# PS_DC-DC_15V_24V.net
KiCad netlist of a schematic drawn in Altium Designer
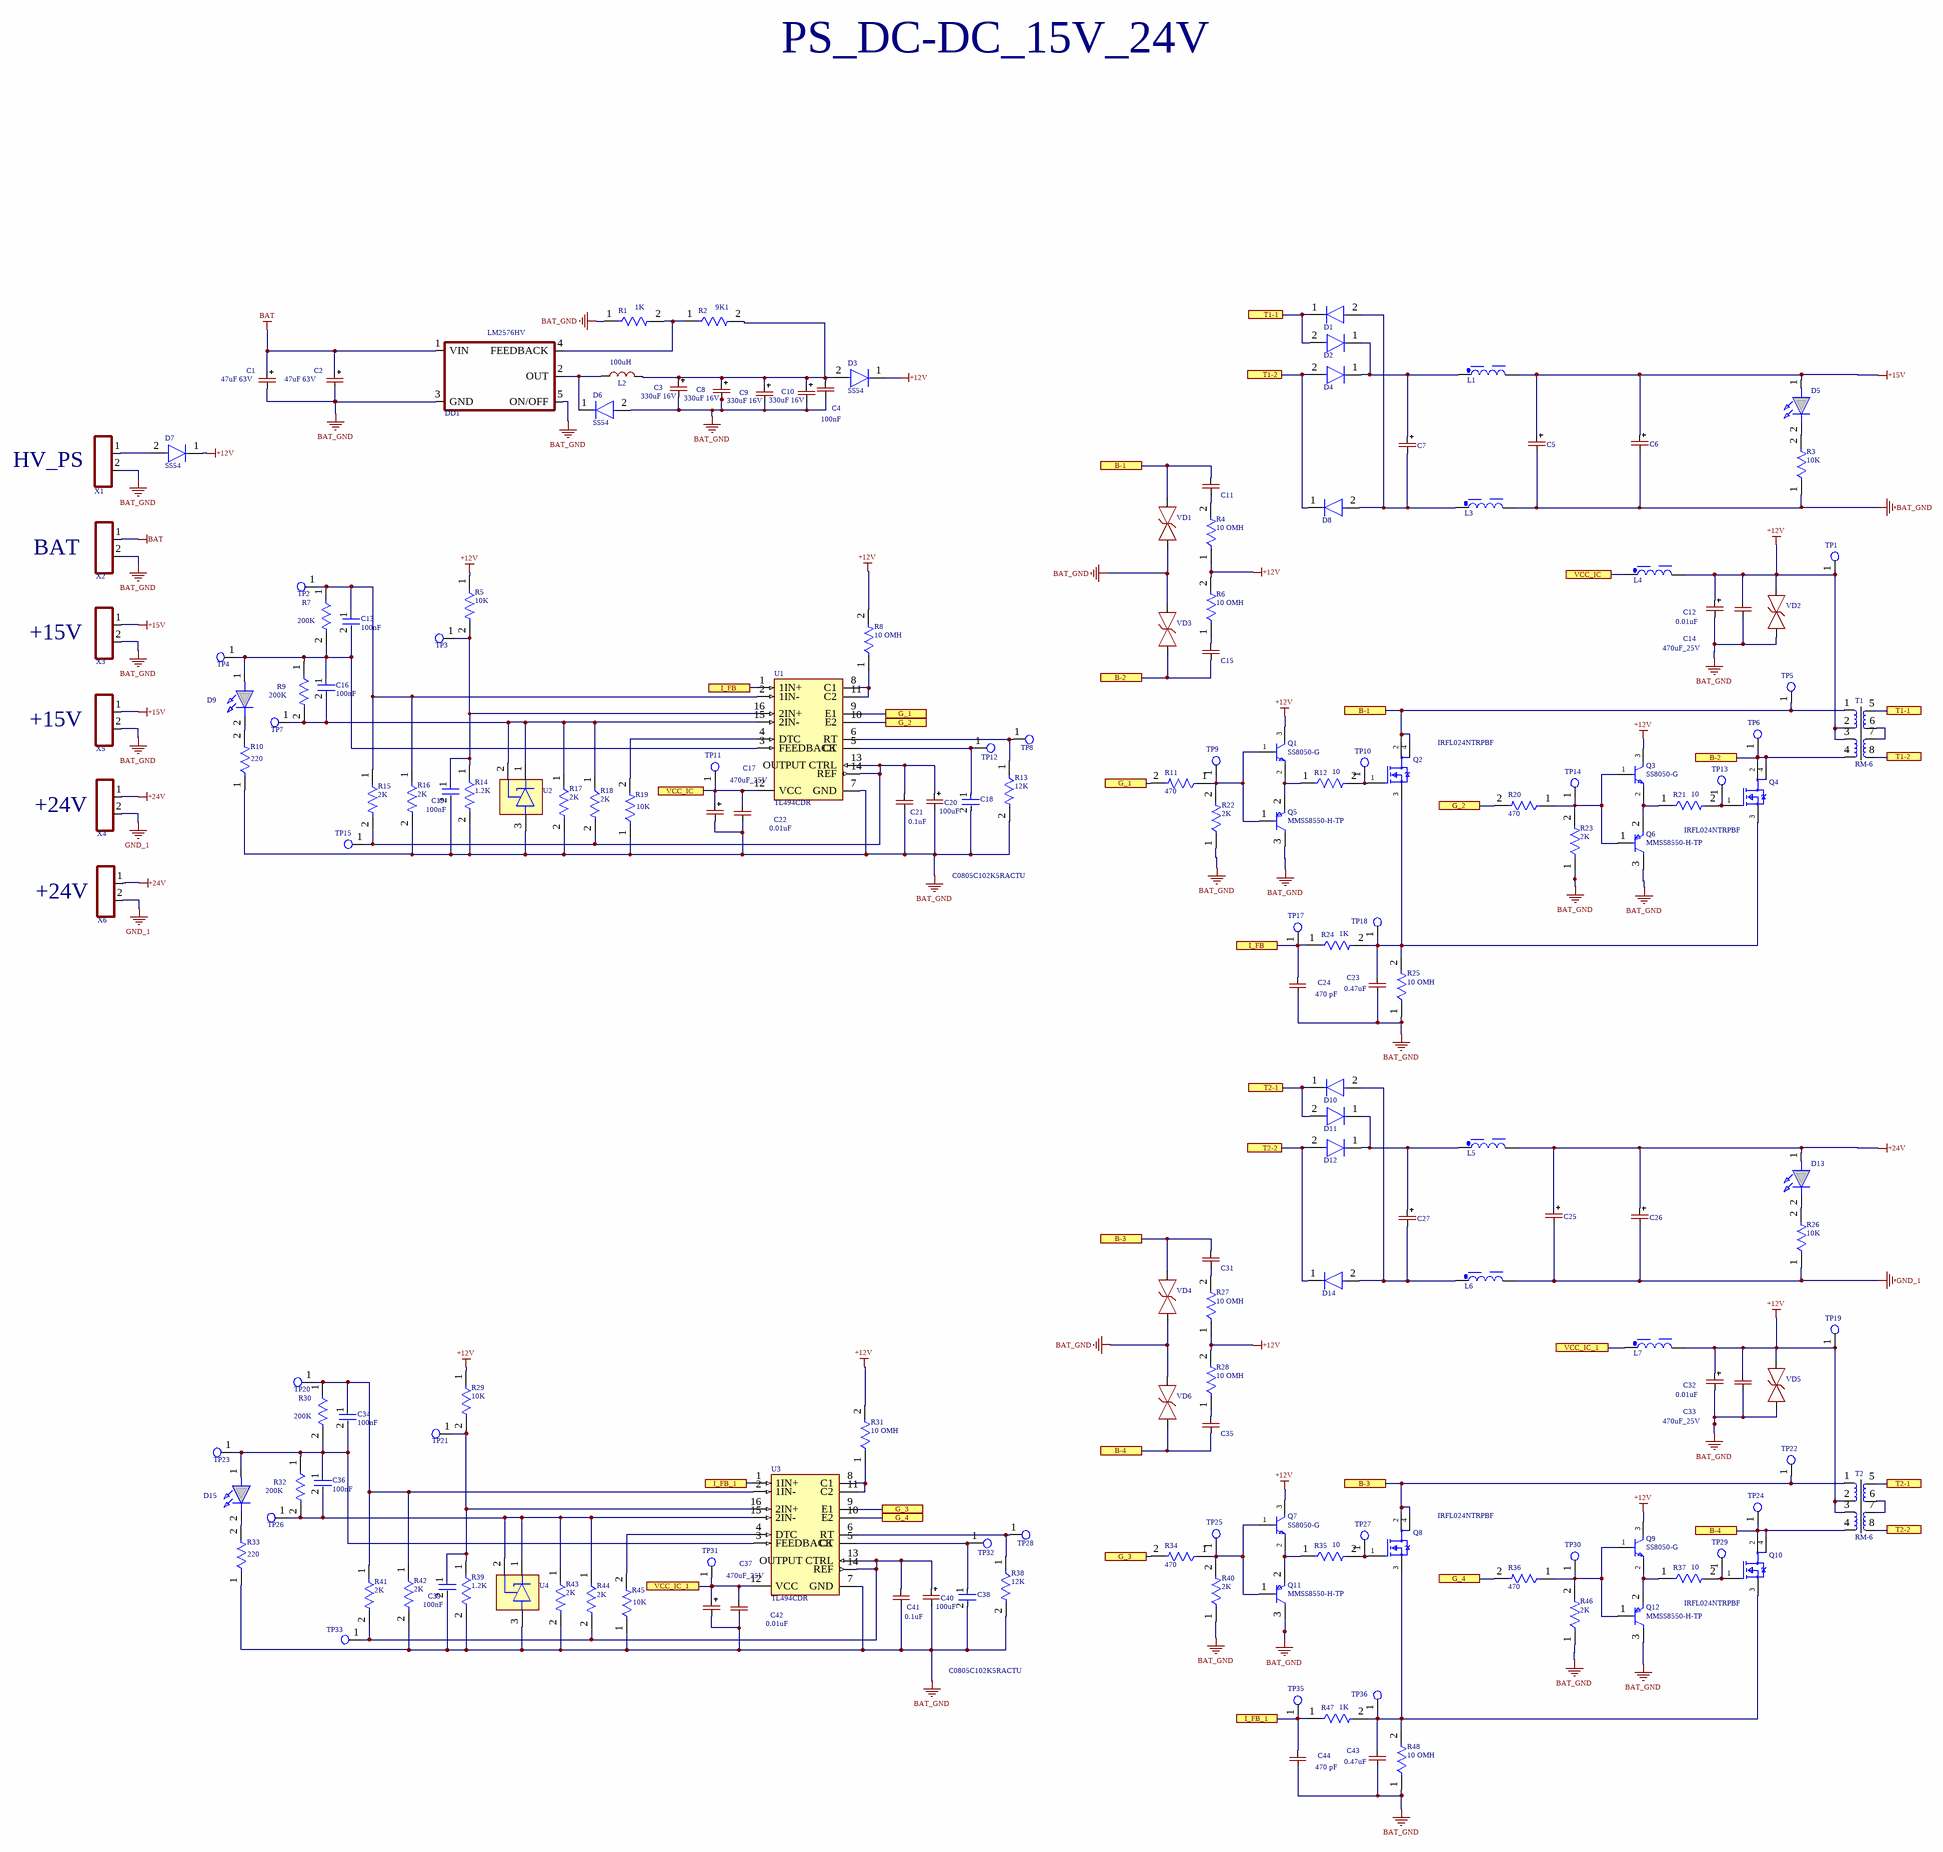
[diagram p0: PS_DC-DC_15V_24V.SchDoc]

(export (version "E")
  (design (tool "Eeschema 10.0.6"))
  (components
    (comp (ref "C1")
      (value "47uF 63V")
      (footprint "CAP_SMD_Size_E")
      (libsource (lib "PASSIVE_COMPONENTS") (part "CAP_POL_SMD"))
    )
    (comp (ref "C2")
      (value "47uF 63V")
      (footprint "CAP_SMD_Size_E")
      (libsource (lib "PASSIVE_COMPONENTS") (part "CAP_POL_SMD"))
    )
    (comp (ref "C3")
      (value "330uF 16V")
      (footprint "CAP_SMD_Size_E")
      (libsource (lib "PASSIVE_COMPONENTS") (part "CAP_POL_SMD"))
    )
    (comp (ref "C4")
      (value "100nF")
      (footprint "CAP-0805")
      (description "1uF ±10% 50V X5R 0805 Multilayer Ceramic Capacitors MLCC - SMD/SMT RoHS")
      (fields (field (name "PART NUMBER") "CC0805KKX5R9BB105") (field (name "MANUFACTURER") "Yageo"))
      (libsource (lib "Database_Libs2") (part "CAP-NON-POLAR"))
    )
    (comp (ref "C5")
      (value "CAP-POLAR")
      (footprint "CAP_SMD_Size_G")
      (libsource (lib "PASSIVE_COMPONENTS") (part "CAP-POLAR"))
    )
    (comp (ref "C6")
      (value "CAP-POLAR")
      (footprint "CAP_SMD_Size_G")
      (libsource (lib "PASSIVE_COMPONENTS") (part "CAP-POLAR"))
    )
    (comp (ref "C7")
      (value "CAP-POLAR")
      (footprint "CAP_SMD_Size_G")
      (libsource (lib "PASSIVE_COMPONENTS") (part "CAP-POLAR"))
    )
    (comp (ref "C8")
      (value "330uF 16V")
      (footprint "CAP_SMD_Size_E")
      (libsource (lib "PASSIVE_COMPONENTS") (part "CAP_POL_SMD"))
    )
    (comp (ref "C9")
      (value "330uF 16V")
      (footprint "CAP_SMD_Size_E")
      (libsource (lib "PASSIVE_COMPONENTS") (part "CAP_POL_SMD"))
    )
    (comp (ref "C10")
      (value "330uF 16V")
      (footprint "CAP_SMD_Size_E")
      (libsource (lib "PASSIVE_COMPONENTS") (part "CAP_POL_SMD"))
    )
    (comp (ref "C11")
      (value "CAP-V")
      (footprint "CAP-V")
      (libsource (lib "PASSIVE_COMPONENTS") (part "CAP-V"))
    )
    (comp (ref "C12")
      (value "0.01uF")
      (footprint "CAP-0805")
      (libsource (lib "PASSIVE_COMPONENTS") (part "CAP-NON-POLAR"))
    )
    (comp (ref "C13")
      (value "100nF")
      (footprint "FP-C0805C-DN-MFG")
      (description "CAP CER 10000PF 50V X7R 0805")
      (fields
        (field (name "MANUFACTURER PART NUMBER") "C0805C103J5RACTU")
        (field (name "MANUFACTURER") "KEMET")
      )
      (libsource (lib "Altium Content Vault") (part "b4654b650e69147ec39a6b967a45e02"))
    )
    (comp (ref "C14")
      (value "470uF_25V")
      (footprint "CAP_SMD_Size_G")
      (libsource (lib "PASSIVE_COMPONENTS") (part "CAP-POLAR"))
    )
    (comp (ref "C15")
      (value "CAP-V")
      (footprint "CAP-V")
      (libsource (lib "PASSIVE_COMPONENTS") (part "CAP-V"))
    )
    (comp (ref "C16")
      (value "100nF")
      (footprint "FP-C0805C-DN-MFG")
      (description "CAP CER 10000PF 50V X7R 0805")
      (fields
        (field (name "MANUFACTURER PART NUMBER") "C0805C103J5RACTU")
        (field (name "MANUFACTURER") "KEMET")
      )
      (libsource (lib "Altium Content Vault") (part "b4654b650e69147ec39a6b967a45e02"))
    )
    (comp (ref "C17")
      (value "470uF_25V")
      (footprint "CAP_SMD_Size_G")
      (libsource (lib "PASSIVE_COMPONENTS") (part "CAP-POLAR"))
    )
    (comp (ref "C18")
      (value "C0805C102K5RACTU")
      (footprint "FP-C0805C-DN-MFG")
      (description "CAP CER 1000PF 50V X7R 0805")
      (fields
        (field (name "OCTOPART") "https://octopart.com/c0805c102k5ractu-kemet-93010")
        (field (name "TOLERANCE") "0.1")
      )
      (libsource (lib "Altium Content Vault") (part "b4654b650e69147ec39a6b967a45e02"))
    )
    (comp (ref "C19")
      (value "100nF")
      (footprint "FP-C0805C-DN-MFG")
      (description "CAP CER 10000PF 50V X7R 0805")
      (fields
        (field (name "MANUFACTURER PART NUMBER") "C0805C103J5RACTU")
        (field (name "MANUFACTURER") "KEMET")
      )
      (libsource (lib "Altium Content Vault") (part "b4654b650e69147ec39a6b967a45e02"))
    )
    (comp (ref "C20")
      (value "100uF")
      (footprint "CAP-TAN-D")
      (libsource (lib "PASSIVE_COMPONENTS") (part "CAP-POLAR"))
    )
    (comp (ref "C21")
      (value "0.1uF")
      (footprint "CAP-0805")
      (libsource (lib "PASSIVE_COMPONENTS") (part "CAP-NON-POLAR"))
    )
    (comp (ref "C22")
      (value "0.01uF")
      (footprint "CAP-0805")
      (libsource (lib "PASSIVE_COMPONENTS") (part "CAP-NON-POLAR"))
    )
    (comp (ref "C23")
      (value "0.47uF")
      (footprint "CAP-0805")
      (libsource (lib "PASSIVE_COMPONENTS") (part "CAP-NON-POLAR"))
    )
    (comp (ref "C24")
      (value "470 pF")
      (footprint "CAP-0805")
      (libsource (lib "PASSIVE_COMPONENTS") (part "CAP-NON-POLAR"))
    )
    (comp (ref "C25")
      (value "CAP-POLAR")
      (footprint "CAP_SMD_Size_G")
      (libsource (lib "PASSIVE_COMPONENTS") (part "CAP-POLAR"))
    )
    (comp (ref "C26")
      (value "CAP-POLAR")
      (footprint "CAP_SMD_Size_G")
      (libsource (lib "PASSIVE_COMPONENTS") (part "CAP-POLAR"))
    )
    (comp (ref "C27")
      (value "CAP-POLAR")
      (footprint "CAP_SMD_Size_G")
      (libsource (lib "PASSIVE_COMPONENTS") (part "CAP-POLAR"))
    )
    (comp (ref "C31")
      (value "CAP-V")
      (footprint "CAP-V")
      (libsource (lib "PASSIVE_COMPONENTS") (part "CAP-V"))
    )
    (comp (ref "C32")
      (value "0.01uF")
      (footprint "CAP-0805")
      (libsource (lib "PASSIVE_COMPONENTS") (part "CAP-NON-POLAR"))
    )
    (comp (ref "C33")
      (value "470uF_25V")
      (footprint "CAP_SMD_Size_G")
      (libsource (lib "PASSIVE_COMPONENTS") (part "CAP-POLAR"))
    )
    (comp (ref "C34")
      (value "100nF")
      (footprint "FP-C0805C-DN-MFG")
      (description "CAP CER 10000PF 50V X7R 0805")
      (fields
        (field (name "MANUFACTURER PART NUMBER") "C0805C103J5RACTU")
        (field (name "MANUFACTURER") "KEMET")
      )
      (libsource (lib "Altium Content Vault") (part "b4654b650e69147ec39a6b967a45e02"))
    )
    (comp (ref "C35")
      (value "CAP-V")
      (footprint "CAP-V")
      (libsource (lib "PASSIVE_COMPONENTS") (part "CAP-V"))
    )
    (comp (ref "C36")
      (value "100nF")
      (footprint "FP-C0805C-DN-MFG")
      (description "CAP CER 10000PF 50V X7R 0805")
      (fields
        (field (name "MANUFACTURER PART NUMBER") "C0805C103J5RACTU")
        (field (name "MANUFACTURER") "KEMET")
      )
      (libsource (lib "Altium Content Vault") (part "b4654b650e69147ec39a6b967a45e02"))
    )
    (comp (ref "C37")
      (value "470uF_25V")
      (footprint "CAP_SMD_Size_G")
      (libsource (lib "PASSIVE_COMPONENTS") (part "CAP-POLAR"))
    )
    (comp (ref "C38")
      (value "C0805C102K5RACTU")
      (footprint "FP-C0805C-DN-MFG")
      (description "CAP CER 1000PF 50V X7R 0805")
      (fields
        (field (name "OCTOPART") "https://octopart.com/c0805c102k5ractu-kemet-93010")
        (field (name "TOLERANCE") "0.1")
      )
      (libsource (lib "Altium Content Vault") (part "b4654b650e69147ec39a6b967a45e02"))
    )
    (comp (ref "C39")
      (value "100nF")
      (footprint "FP-C0805C-DN-MFG")
      (description "CAP CER 10000PF 50V X7R 0805")
      (fields
        (field (name "MANUFACTURER PART NUMBER") "C0805C103J5RACTU")
        (field (name "MANUFACTURER") "KEMET")
      )
      (libsource (lib "Altium Content Vault") (part "b4654b650e69147ec39a6b967a45e02"))
    )
    (comp (ref "C40")
      (value "100uF")
      (footprint "CAP-TAN-D")
      (libsource (lib "PASSIVE_COMPONENTS") (part "CAP-POLAR"))
    )
    (comp (ref "C41")
      (value "0.1uF")
      (footprint "CAP-0805")
      (libsource (lib "PASSIVE_COMPONENTS") (part "CAP-NON-POLAR"))
    )
    (comp (ref "C42")
      (value "0.01uF")
      (footprint "CAP-0805")
      (libsource (lib "PASSIVE_COMPONENTS") (part "CAP-NON-POLAR"))
    )
    (comp (ref "C43")
      (value "0.47uF")
      (footprint "CAP-0805")
      (libsource (lib "PASSIVE_COMPONENTS") (part "CAP-NON-POLAR"))
    )
    (comp (ref "C44")
      (value "470 pF")
      (footprint "CAP-0805")
      (libsource (lib "PASSIVE_COMPONENTS") (part "CAP-NON-POLAR"))
    )
    (comp (ref "D1") (value "US1G") (footprint "DO-214AA") (libsource (lib "Diodes") (part "US1G")))
    (comp (ref "D2") (value "US1G") (footprint "DO-214AA") (libsource (lib "Diodes") (part "US1G")))
    (comp (ref "D3")
      (value "SS54")
      (footprint "DO214-AB")
      (description "ES3D-DO214AB")
      (libsource (lib "Diodes") (part "ES3D-DO214AB"))
    )
    (comp (ref "D4") (value "US1G") (footprint "DO-214AA") (libsource (lib "Diodes") (part "US1G")))
    (comp (ref "D5")
      (value "151031YS06000")
      (footprint "LED_RED")
      (description "WURTH ELEKTRONIK - 151031YS06000 - LED, Yellow, Through Hole, T-1 (3mm), 30 mA, 2 V, 590 nm")
      (fields (field (name "MOUSER PART NUMBER") "710-151031YS06000"))
      (libsource (lib "Optic-LED") (part "LED"))
    )
    (comp (ref "D6")
      (value "SS54")
      (footprint "DO214-AB")
      (description "ES3D-DO214AB")
      (libsource (lib "Diodes") (part "ES3D-DO214AB"))
    )
    (comp (ref "D7")
      (value "SS54")
      (footprint "DO214-AB")
      (description "ES3D-DO214AB")
      (libsource (lib "Diodes") (part "ES3D-DO214AB"))
    )
    (comp (ref "D8") (value "US1G") (footprint "DO-214AA") (libsource (lib "Diodes") (part "US1G")))
    (comp (ref "D9")
      (value "151031YS06000")
      (footprint "LED_RED")
      (description "WURTH ELEKTRONIK - 151031YS06000 - LED, Yellow, Through Hole, T-1 (3mm), 30 mA, 2 V, 590 nm")
      (fields (field (name "MOUSER PART NUMBER") "710-151031YS06000"))
      (libsource (lib "Optic-LED") (part "LED"))
    )
    (comp (ref "D10") (value "US1G") (footprint "DO-214AA") (libsource (lib "Diodes") (part "US1G")))
    (comp (ref "D11") (value "US1G") (footprint "DO-214AA") (libsource (lib "Diodes") (part "US1G")))
    (comp (ref "D12") (value "US1G") (footprint "DO-214AA") (libsource (lib "Diodes") (part "US1G")))
    (comp (ref "D13")
      (value "151031YS06000")
      (footprint "LED_RED")
      (description "WURTH ELEKTRONIK - 151031YS06000 - LED, Yellow, Through Hole, T-1 (3mm), 30 mA, 2 V, 590 nm")
      (fields (field (name "MOUSER PART NUMBER") "710-151031YS06000"))
      (libsource (lib "Optic-LED") (part "LED"))
    )
    (comp (ref "D14") (value "US1G") (footprint "DO-214AA") (libsource (lib "Diodes") (part "US1G")))
    (comp (ref "D15")
      (value "151031YS06000")
      (footprint "LED_RED")
      (description "WURTH ELEKTRONIK - 151031YS06000 - LED, Yellow, Through Hole, T-1 (3mm), 30 mA, 2 V, 590 nm")
      (fields (field (name "MOUSER PART NUMBER") "710-151031YS06000"))
      (libsource (lib "Optic-LED") (part "LED"))
    )
    (comp (ref "DD1")
      (value "LM2576HV")
      (footprint "TO-263-5")
      (libsource (lib "LM2576HV") (part "LM2576HV"))
    )
    (comp (ref "L1")
      (value "390µH, 0.38A")
      (footprint "WE-PD2_7850")
      (description "WE-PD2 SMT Power Inductor, size 7850, 390µH, 0.38A, 1.77Ω")
      (fields
        (field (name "MANUFACTURER PART NUMBER") "744775239")
        (field (name "MANUFACTURER") "Wurth Elektronik")
      )
      (libsource (lib "WE-PD2 (rev22d)") (part "744775239"))
    )
    (comp (ref "L2") (value "100uH") (footprint "CDRH127") (libsource (lib "CDRH127") (part "IND-CONST")))
    (comp (ref "L3")
      (value "390µH, 0.38A")
      (footprint "WE-PD2_7850")
      (description "WE-PD2 SMT Power Inductor, size 7850, 390µH, 0.38A, 1.77Ω")
      (fields
        (field (name "MANUFACTURER PART NUMBER") "744775239")
        (field (name "MANUFACTURER") "Wurth Elektronik")
      )
      (libsource (lib "WE-PD2 (rev22d)") (part "744775239"))
    )
    (comp (ref "L4")
      (value "390µH, 0.38A")
      (footprint "WE-PD2_7850")
      (description "WE-PD2 SMT Power Inductor, size 7850, 390µH, 0.38A, 1.77Ω")
      (fields
        (field (name "MANUFACTURER PART NUMBER") "744775239")
        (field (name "MANUFACTURER") "Wurth Elektronik")
      )
      (libsource (lib "WE-PD2 (rev22d)") (part "744775239"))
    )
    (comp (ref "L5")
      (value "390µH, 0.38A")
      (footprint "WE-PD2_7850")
      (description "WE-PD2 SMT Power Inductor, size 7850, 390µH, 0.38A, 1.77Ω")
      (fields
        (field (name "MANUFACTURER PART NUMBER") "744775239")
        (field (name "MANUFACTURER") "Wurth Elektronik")
      )
      (libsource (lib "WE-PD2 (rev22d)") (part "744775239"))
    )
    (comp (ref "L6")
      (value "390µH, 0.38A")
      (footprint "WE-PD2_7850")
      (description "WE-PD2 SMT Power Inductor, size 7850, 390µH, 0.38A, 1.77Ω")
      (fields
        (field (name "MANUFACTURER PART NUMBER") "744775239")
        (field (name "MANUFACTURER") "Wurth Elektronik")
      )
      (libsource (lib "WE-PD2 (rev22d)") (part "744775239"))
    )
    (comp (ref "L7")
      (value "390µH, 0.38A")
      (footprint "WE-PD2_7850")
      (description "WE-PD2 SMT Power Inductor, size 7850, 390µH, 0.38A, 1.77Ω")
      (fields
        (field (name "MANUFACTURER PART NUMBER") "744775239")
        (field (name "MANUFACTURER") "Wurth Elektronik")
      )
      (libsource (lib "WE-PD2 (rev22d)") (part "744775239"))
    )
    (comp (ref "Q1")
      (value "SS8050-G")
      (footprint "FP-SS8050-G-MFG")
      (description "NPN TRANSISTOR 1.5A 40V SOT-23 R")
      (libsource (lib "Altium Content Vault") (part "2a1388f82443b098dcd57d24ac7632d"))
    )
    (comp (ref "Q2")
      (value "IRFL024NTRPBF")
      (footprint "FP-PG-SOT223-3-IPC_B")
      (description "MOSFET N-CH 55V 2.8A SOT223")
      (libsource (lib "Altium Content Vault") (part "7f70c8421781a2c4d0598199639518f"))
    )
    (comp (ref "Q3")
      (value "SS8050-G")
      (footprint "FP-SS8050-G-MFG")
      (description "NPN TRANSISTOR 1.5A 40V SOT-23 R")
      (libsource (lib "Altium Content Vault") (part "2a1388f82443b098dcd57d24ac7632d"))
    )
    (comp (ref "Q4")
      (value "IRFL024NTRPBF")
      (footprint "FP-PG-SOT223-3-IPC_B")
      (description "MOSFET N-CH 55V 2.8A SOT223")
      (libsource (lib "Altium Content Vault") (part "7f70c8421781a2c4d0598199639518f"))
    )
    (comp (ref "Q5")
      (value "MMSS8550-H-TP")
      (footprint "FP-SOT-23-IPC_B")
      (description "TRANS PNP 25V 1.5A SOT23")
      (libsource (lib "Altium Content Vault") (part "0e8486ed3b47d9c69b8404ba87cf0f7"))
    )
    (comp (ref "Q6")
      (value "MMSS8550-H-TP")
      (footprint "FP-SOT-23-IPC_B")
      (description "TRANS PNP 25V 1.5A SOT23")
      (libsource (lib "Altium Content Vault") (part "0e8486ed3b47d9c69b8404ba87cf0f7"))
    )
    (comp (ref "Q7")
      (value "SS8050-G")
      (footprint "FP-SS8050-G-MFG")
      (description "NPN TRANSISTOR 1.5A 40V SOT-23 R")
      (libsource (lib "Altium Content Vault") (part "2a1388f82443b098dcd57d24ac7632d"))
    )
    (comp (ref "Q8")
      (value "IRFL024NTRPBF")
      (footprint "FP-PG-SOT223-3-IPC_B")
      (description "MOSFET N-CH 55V 2.8A SOT223")
      (libsource (lib "Altium Content Vault") (part "7f70c8421781a2c4d0598199639518f"))
    )
    (comp (ref "Q9")
      (value "SS8050-G")
      (footprint "FP-SS8050-G-MFG")
      (description "NPN TRANSISTOR 1.5A 40V SOT-23 R")
      (libsource (lib "Altium Content Vault") (part "2a1388f82443b098dcd57d24ac7632d"))
    )
    (comp (ref "Q10")
      (value "IRFL024NTRPBF")
      (footprint "FP-PG-SOT223-3-IPC_B")
      (description "MOSFET N-CH 55V 2.8A SOT223")
      (libsource (lib "Altium Content Vault") (part "7f70c8421781a2c4d0598199639518f"))
    )
    (comp (ref "Q11")
      (value "MMSS8550-H-TP")
      (footprint "FP-SOT-23-IPC_B")
      (description "TRANS PNP 25V 1.5A SOT23")
      (libsource (lib "Altium Content Vault") (part "0e8486ed3b47d9c69b8404ba87cf0f7"))
    )
    (comp (ref "Q12")
      (value "MMSS8550-H-TP")
      (footprint "FP-SOT-23-IPC_B")
      (description "TRANS PNP 25V 1.5A SOT23")
      (libsource (lib "Altium Content Vault") (part "0e8486ed3b47d9c69b8404ba87cf0f7"))
    )
    (comp (ref "R1")
      (value "1K")
      (footprint "RES-0805")
      (description "10K")
      (libsource (lib "PASSIVE_COMPONENTS") (part "RES-CONST"))
    )
    (comp (ref "R2")
      (value "9K1")
      (footprint "RES-0805")
      (description "10K")
      (libsource (lib "PASSIVE_COMPONENTS") (part "RES-CONST"))
    )
    (comp (ref "R3")
      (value "10K")
      (footprint "RES-0805")
      (libsource (lib "PASSIVE_COMPONENTS") (part "RES-CONST"))
    )
    (comp (ref "R4")
      (value "10 OMH")
      (footprint "RES-1206")
      (libsource (lib "PASSIVE_COMPONENTS") (part "RES-CONST"))
    )
    (comp (ref "R5")
      (value "10K")
      (footprint "FP-CRCW0805-e3-MFG")
      (description "RES Thick Film, 2kΩ, 1%, 0.125W, 100ppm/°C, 0805")
      (fields (field (name "TOLERANCE") "1%"))
      (libsource (lib "Pasive_components") (part "CMP-2001-04908-2"))
    )
    (comp (ref "R6")
      (value "10 OMH")
      (footprint "RES-1206")
      (libsource (lib "PASSIVE_COMPONENTS") (part "RES-CONST"))
    )
    (comp (ref "R7")
      (value "200K")
      (footprint "FP-CRCW0805-e3-MFG")
      (description "RES Thick Film, 2kΩ, 1%, 0.125W, 100ppm/°C, 0805")
      (fields (field (name "TOLERANCE") "1%"))
      (libsource (lib "Pasive_components") (part "CMP-2001-04908-2"))
    )
    (comp (ref "R8")
      (value "10 OMH")
      (footprint "RES-1206")
      (libsource (lib "PASSIVE_COMPONENTS") (part "RES-CONST"))
    )
    (comp (ref "R9")
      (value "200K")
      (footprint "FP-CRCW0805-e3-MFG")
      (description "RES Thick Film, 2kΩ, 1%, 0.125W, 100ppm/°C, 0805")
      (fields (field (name "TOLERANCE") "1%"))
      (libsource (lib "Pasive_components") (part "CMP-2001-04908-2"))
    )
    (comp (ref "R10")
      (value "220")
      (footprint "RES-0805")
      (libsource (lib "PASSIVE_COMPONENTS") (part "RES-CONST"))
    )
    (comp (ref "R11")
      (value "470")
      (footprint "RES-0805")
      (libsource (lib "PASSIVE_COMPONENTS") (part "RES-CONST"))
    )
    (comp (ref "R12")
      (value "10")
      (footprint "RES-0805")
      (libsource (lib "PASSIVE_COMPONENTS") (part "RES-CONST"))
    )
    (comp (ref "R13")
      (value "12K")
      (footprint "FP-CRCW0805-e3-MFG")
      (description "RES Thick Film, 12kΩ, 1%, 0.125W, 100ppm/°C, 0805")
      (fields (field (name "TOLERANCE") "1%"))
      (libsource (lib "Pasive_components") (part "CMP-2001-04908-2"))
    )
    (comp (ref "R14")
      (value "1.2K")
      (footprint "FP-CRCW0805-e3-MFG")
      (description "RES Thick Film, 2kΩ, 1%, 0.125W, 100ppm/°C, 0805")
      (fields (field (name "TOLERANCE") "1%"))
      (libsource (lib "Pasive_components") (part "CMP-2001-04908-2"))
    )
    (comp (ref "R15")
      (value "2K")
      (footprint "FP-CRCW0805-e3-MFG")
      (description "RES Thick Film, 2kΩ, 1%, 0.125W, 100ppm/°C, 0805")
      (fields (field (name "TOLERANCE") "1%"))
      (libsource (lib "Pasive_components") (part "CMP-2001-04908-2"))
    )
    (comp (ref "R16")
      (value "2K")
      (footprint "FP-CRCW0805-e3-MFG")
      (description "RES Thick Film, 82kΩ, 1%, 0.125W, 100ppm/°C, 0805")
      (fields (field (name "TOLERANCE") "1%"))
      (libsource (lib "Pasive_components") (part "CMP-2001-04908-2"))
    )
    (comp (ref "R17")
      (value "2K")
      (footprint "FP-CRCW0805-e3-MFG")
      (description "RES Thick Film, 2kΩ, 1%, 0.125W, 100ppm/°C, 0805")
      (fields (field (name "TOLERANCE") "1%"))
      (libsource (lib "Pasive_components") (part "CMP-2001-04908-2"))
    )
    (comp (ref "R18")
      (value "2K")
      (footprint "FP-CRCW0805-e3-MFG")
      (description "RES Thick Film, 2kΩ, 1%, 0.125W, 100ppm/°C, 0805")
      (fields (field (name "TOLERANCE") "1%"))
      (libsource (lib "Pasive_components") (part "CMP-2001-04908-2"))
    )
    (comp (ref "R19")
      (value "10K")
      (footprint "RES-0805")
      (libsource (lib "PASSIVE_COMPONENTS") (part "RES-CONST"))
    )
    (comp (ref "R20")
      (value "470")
      (footprint "RES-0805")
      (libsource (lib "PASSIVE_COMPONENTS") (part "RES-CONST"))
    )
    (comp (ref "R21")
      (value "10")
      (footprint "RES-0805")
      (libsource (lib "PASSIVE_COMPONENTS") (part "RES-CONST"))
    )
    (comp (ref "R22")
      (value "2K")
      (footprint "RES-0805")
      (libsource (lib "PASSIVE_COMPONENTS") (part "RES-CONST"))
    )
    (comp (ref "R23")
      (value "2K")
      (footprint "RES-0805")
      (libsource (lib "PASSIVE_COMPONENTS") (part "RES-CONST"))
    )
    (comp (ref "R24")
      (value "1K")
      (footprint "RES-0805")
      (libsource (lib "PASSIVE_COMPONENTS") (part "RES-CONST"))
    )
    (comp (ref "R25")
      (value "10 OMH")
      (footprint "RES-2512")
      (libsource (lib "PASSIVE_COMPONENTS") (part "RES-CONST"))
    )
    (comp (ref "R26")
      (value "10K")
      (footprint "RES-0805")
      (libsource (lib "PASSIVE_COMPONENTS") (part "RES-CONST"))
    )
    (comp (ref "R27")
      (value "10 OMH")
      (footprint "RES-1206")
      (libsource (lib "PASSIVE_COMPONENTS") (part "RES-CONST"))
    )
    (comp (ref "R28")
      (value "10 OMH")
      (footprint "RES-1206")
      (libsource (lib "PASSIVE_COMPONENTS") (part "RES-CONST"))
    )
    (comp (ref "R29")
      (value "10K")
      (footprint "FP-CRCW0805-e3-MFG")
      (description "RES Thick Film, 2kΩ, 1%, 0.125W, 100ppm/°C, 0805")
      (fields (field (name "TOLERANCE") "1%"))
      (libsource (lib "Pasive_components") (part "CMP-2001-04908-2"))
    )
    (comp (ref "R30")
      (value "200K")
      (footprint "FP-CRCW0805-e3-MFG")
      (description "RES Thick Film, 2kΩ, 1%, 0.125W, 100ppm/°C, 0805")
      (fields (field (name "TOLERANCE") "1%"))
      (libsource (lib "Pasive_components") (part "CMP-2001-04908-2"))
    )
    (comp (ref "R31")
      (value "10 OMH")
      (footprint "RES-1206")
      (libsource (lib "PASSIVE_COMPONENTS") (part "RES-CONST"))
    )
    (comp (ref "R32")
      (value "200K")
      (footprint "FP-CRCW0805-e3-MFG")
      (description "RES Thick Film, 2kΩ, 1%, 0.125W, 100ppm/°C, 0805")
      (fields (field (name "TOLERANCE") "1%"))
      (libsource (lib "Pasive_components") (part "CMP-2001-04908-2"))
    )
    (comp (ref "R33")
      (value "220")
      (footprint "RES-0805")
      (libsource (lib "PASSIVE_COMPONENTS") (part "RES-CONST"))
    )
    (comp (ref "R34")
      (value "470")
      (footprint "RES-0805")
      (libsource (lib "PASSIVE_COMPONENTS") (part "RES-CONST"))
    )
    (comp (ref "R35")
      (value "10")
      (footprint "RES-0805")
      (libsource (lib "PASSIVE_COMPONENTS") (part "RES-CONST"))
    )
    (comp (ref "R36")
      (value "470")
      (footprint "RES-0805")
      (libsource (lib "PASSIVE_COMPONENTS") (part "RES-CONST"))
    )
    (comp (ref "R37")
      (value "10")
      (footprint "RES-0805")
      (libsource (lib "PASSIVE_COMPONENTS") (part "RES-CONST"))
    )
    (comp (ref "R38")
      (value "12K")
      (footprint "FP-CRCW0805-e3-MFG")
      (description "RES Thick Film, 12kΩ, 1%, 0.125W, 100ppm/°C, 0805")
      (fields (field (name "TOLERANCE") "1%"))
      (libsource (lib "Pasive_components") (part "CMP-2001-04908-2"))
    )
    (comp (ref "R39")
      (value "1.2K")
      (footprint "FP-CRCW0805-e3-MFG")
      (description "RES Thick Film, 2kΩ, 1%, 0.125W, 100ppm/°C, 0805")
      (fields (field (name "TOLERANCE") "1%"))
      (libsource (lib "Pasive_components") (part "CMP-2001-04908-2"))
    )
    (comp (ref "R40")
      (value "2K")
      (footprint "RES-0805")
      (libsource (lib "PASSIVE_COMPONENTS") (part "RES-CONST"))
    )
    (comp (ref "R41")
      (value "2K")
      (footprint "FP-CRCW0805-e3-MFG")
      (description "RES Thick Film, 2kΩ, 1%, 0.125W, 100ppm/°C, 0805")
      (fields (field (name "TOLERANCE") "1%"))
      (libsource (lib "Pasive_components") (part "CMP-2001-04908-2"))
    )
    (comp (ref "R42")
      (value "2K")
      (footprint "FP-CRCW0805-e3-MFG")
      (description "RES Thick Film, 82kΩ, 1%, 0.125W, 100ppm/°C, 0805")
      (fields (field (name "TOLERANCE") "1%"))
      (libsource (lib "Pasive_components") (part "CMP-2001-04908-2"))
    )
    (comp (ref "R43")
      (value "2K")
      (footprint "FP-CRCW0805-e3-MFG")
      (description "RES Thick Film, 2kΩ, 1%, 0.125W, 100ppm/°C, 0805")
      (fields (field (name "TOLERANCE") "1%"))
      (libsource (lib "Pasive_components") (part "CMP-2001-04908-2"))
    )
    (comp (ref "R44")
      (value "2K")
      (footprint "FP-CRCW0805-e3-MFG")
      (description "RES Thick Film, 2kΩ, 1%, 0.125W, 100ppm/°C, 0805")
      (fields (field (name "TOLERANCE") "1%"))
      (libsource (lib "Pasive_components") (part "CMP-2001-04908-2"))
    )
    (comp (ref "R45")
      (value "10K")
      (footprint "RES-0805")
      (libsource (lib "PASSIVE_COMPONENTS") (part "RES-CONST"))
    )
    (comp (ref "R46")
      (value "2K")
      (footprint "RES-0805")
      (libsource (lib "PASSIVE_COMPONENTS") (part "RES-CONST"))
    )
    (comp (ref "R47")
      (value "1K")
      (footprint "RES-0805")
      (libsource (lib "PASSIVE_COMPONENTS") (part "RES-CONST"))
    )
    (comp (ref "R48")
      (value "10 OMH")
      (footprint "RES-2512")
      (libsource (lib "PASSIVE_COMPONENTS") (part "RES-CONST"))
    )
    (comp (ref "T1")
      (value "RM-6")
      (footprint "TRANS_RM6")
      (libsource (lib "Transformers") (part "RM_6_12-12-18-18"))
    )
    (comp (ref "T2")
      (value "RM-6")
      (footprint "TRANS_RM6")
      (libsource (lib "Transformers") (part "RM_6_12-12-18-18"))
    )
    (comp (ref "TP1")
      (value "~")
      (footprint "Test_Point")
      (description "Test_Point")
      (libsource (lib "Connectors") (part "TP_PCB?"))
    )
    (comp (ref "TP2")
      (value "Test_Point_PCB")
      (footprint "Test_Point")
      (description "Test_Point")
      (libsource (lib "Test_Point") (part "TP_PCB?"))
    )
    (comp (ref "TP3")
      (value "Test_Point_PCB")
      (footprint "Test_Point")
      (description "Test_Point")
      (libsource (lib "Test_Point") (part "TP_PCB?"))
    )
    (comp (ref "TP4")
      (value "Test_Point_PCB")
      (footprint "Test_Point")
      (description "Test_Point")
      (libsource (lib "Test_Point") (part "TP_PCB?"))
    )
    (comp (ref "TP5")
      (value "~")
      (footprint "Test_Point")
      (description "Test_Point")
      (libsource (lib "Connectors") (part "TP_PCB?"))
    )
    (comp (ref "TP6")
      (value "~")
      (footprint "Test_Point")
      (description "Test_Point")
      (libsource (lib "Connectors") (part "TP_PCB?"))
    )
    (comp (ref "TP7")
      (value "~")
      (footprint "Test_Point")
      (description "Test_Point")
      (libsource (lib "Connectors") (part "TP_PCB?"))
    )
    (comp (ref "TP8")
      (value "~")
      (footprint "Test_Point")
      (description "Test_Point")
      (libsource (lib "Connectors") (part "TP_PCB?"))
    )
    (comp (ref "TP9")
      (value "~")
      (footprint "Test_Point")
      (description "Test_Point")
      (libsource (lib "Connectors") (part "TP_PCB?"))
    )
    (comp (ref "TP10")
      (value "~")
      (footprint "Test_Point")
      (description "Test_Point")
      (libsource (lib "Connectors") (part "TP_PCB?"))
    )
    (comp (ref "TP11")
      (value "~")
      (footprint "Test_Point")
      (description "Test_Point")
      (libsource (lib "Connectors") (part "TP_PCB?"))
    )
    (comp (ref "TP12")
      (value "Test_Point_PCB")
      (footprint "Test_Point")
      (description "Test_Point")
      (libsource (lib "Test_Point") (part "TP_PCB?"))
    )
    (comp (ref "TP13")
      (value "~")
      (footprint "Test_Point")
      (description "Test_Point")
      (libsource (lib "Connectors") (part "TP_PCB?"))
    )
    (comp (ref "TP14")
      (value "~")
      (footprint "Test_Point")
      (description "Test_Point")
      (libsource (lib "Connectors") (part "TP_PCB?"))
    )
    (comp (ref "TP15")
      (value "Test_Point_PCB")
      (footprint "Test_Point")
      (description "Test_Point")
      (libsource (lib "Test_Point") (part "TP_PCB?"))
    )
    (comp (ref "TP17")
      (value "~")
      (footprint "Test_Point")
      (description "Test_Point")
      (libsource (lib "Connectors") (part "TP_PCB?"))
    )
    (comp (ref "TP18")
      (value "~")
      (footprint "Test_Point")
      (description "Test_Point")
      (libsource (lib "Connectors") (part "TP_PCB?"))
    )
    (comp (ref "TP19")
      (value "~")
      (footprint "Test_Point")
      (description "Test_Point")
      (libsource (lib "Connectors") (part "TP_PCB?"))
    )
    (comp (ref "TP20")
      (value "Test_Point_PCB")
      (footprint "Test_Point")
      (description "Test_Point")
      (libsource (lib "Test_Point") (part "TP_PCB?"))
    )
    (comp (ref "TP21")
      (value "Test_Point_PCB")
      (footprint "Test_Point")
      (description "Test_Point")
      (libsource (lib "Test_Point") (part "TP_PCB?"))
    )
    (comp (ref "TP22")
      (value "~")
      (footprint "Test_Point")
      (description "Test_Point")
      (libsource (lib "Connectors") (part "TP_PCB?"))
    )
    (comp (ref "TP23")
      (value "Test_Point_PCB")
      (footprint "Test_Point")
      (description "Test_Point")
      (libsource (lib "Test_Point") (part "TP_PCB?"))
    )
    (comp (ref "TP24")
      (value "~")
      (footprint "Test_Point")
      (description "Test_Point")
      (libsource (lib "Connectors") (part "TP_PCB?"))
    )
    (comp (ref "TP25")
      (value "~")
      (footprint "Test_Point")
      (description "Test_Point")
      (libsource (lib "Connectors") (part "TP_PCB?"))
    )
    (comp (ref "TP26")
      (value "~")
      (footprint "Test_Point")
      (description "Test_Point")
      (libsource (lib "Connectors") (part "TP_PCB?"))
    )
    (comp (ref "TP27")
      (value "~")
      (footprint "Test_Point")
      (description "Test_Point")
      (libsource (lib "Connectors") (part "TP_PCB?"))
    )
    (comp (ref "TP28")
      (value "~")
      (footprint "Test_Point")
      (description "Test_Point")
      (libsource (lib "Connectors") (part "TP_PCB?"))
    )
    (comp (ref "TP29")
      (value "~")
      (footprint "Test_Point")
      (description "Test_Point")
      (libsource (lib "Connectors") (part "TP_PCB?"))
    )
    (comp (ref "TP30")
      (value "~")
      (footprint "Test_Point")
      (description "Test_Point")
      (libsource (lib "Connectors") (part "TP_PCB?"))
    )
    (comp (ref "TP31")
      (value "~")
      (footprint "Test_Point")
      (description "Test_Point")
      (libsource (lib "Connectors") (part "TP_PCB?"))
    )
    (comp (ref "TP32")
      (value "Test_Point_PCB")
      (footprint "Test_Point")
      (description "Test_Point")
      (libsource (lib "Test_Point") (part "TP_PCB?"))
    )
    (comp (ref "TP33")
      (value "Test_Point_PCB")
      (footprint "Test_Point")
      (description "Test_Point")
      (libsource (lib "Test_Point") (part "TP_PCB?"))
    )
    (comp (ref "TP35")
      (value "~")
      (footprint "Test_Point")
      (description "Test_Point")
      (libsource (lib "Connectors") (part "TP_PCB?"))
    )
    (comp (ref "TP36")
      (value "~")
      (footprint "Test_Point")
      (description "Test_Point")
      (libsource (lib "Connectors") (part "TP_PCB?"))
    )
    (comp (ref "U1")
      (value "TL494CDR")
      (footprint "D0016A_N")
      (fields (field (name "MANUFACTURER") "Texas Instruments"))
      (libsource (lib "Altium Content Vault") (part "TI-494D16"))
    )
    (comp (ref "U2")
      (value "TL431")
      (footprint "TL431_SOT-23-3(A)")
      (description "TL431_SOT-23-3")
      (libsource (lib "Diodes") (part "TL431_SOT-23-3"))
    )
    (comp (ref "U3")
      (value "TL494CDR")
      (footprint "D0016A_N")
      (fields (field (name "MANUFACTURER") "Texas Instruments"))
      (libsource (lib "Altium Content Vault") (part "TI-494D16"))
    )
    (comp (ref "U4")
      (value "TL431")
      (footprint "TL431_SOT-23-3(A)")
      (description "TL431_SOT-23-3")
      (libsource (lib "Diodes") (part "TL431_SOT-23-3"))
    )
    (comp (ref "VD1")
      (value "Suppressor")
      (footprint "P6KE350CA")
      (libsource (lib "Diodes") (part "Suppressor"))
    )
    (comp (ref "VD2")
      (value "Suppressor")
      (footprint "DO-214AA")
      (libsource (lib "Diodes") (part "Suppressor"))
    )
    (comp (ref "VD3")
      (value "Suppressor")
      (footprint "P6KE350CA")
      (libsource (lib "Diodes") (part "Suppressor"))
    )
    (comp (ref "VD4")
      (value "Suppressor")
      (footprint "P6KE350CA")
      (libsource (lib "Diodes") (part "Suppressor"))
    )
    (comp (ref "VD5")
      (value "Suppressor")
      (footprint "DO-214AA")
      (libsource (lib "Diodes") (part "Suppressor"))
    )
    (comp (ref "VD6")
      (value "Suppressor")
      (footprint "P6KE350CA")
      (libsource (lib "Diodes") (part "Suppressor"))
    )
    (comp (ref "X1") (value "CONN-2-PIN") (footprint "XH2-") (libsource (lib "XH 2PIN") (part "CONN-2-PIN")))
    (comp (ref "X2") (value "CONN-2-PIN") (footprint "XH2-") (libsource (lib "XH 2PIN") (part "CONN-2-PIN")))
    (comp (ref "X3") (value "CONN-2-PIN") (footprint "XH2-") (libsource (lib "XH 2PIN") (part "CONN-2-PIN")))
    (comp (ref "X4") (value "CONN-2-PIN") (footprint "XH2-") (libsource (lib "XH 2PIN") (part "CONN-2-PIN")))
    (comp (ref "X5") (value "CONN-2-PIN") (footprint "XH2-") (libsource (lib "XH 2PIN") (part "CONN-2-PIN")))
    (comp (ref "X6") (value "CONN-2-PIN") (footprint "XH2-") (libsource (lib "XH 2PIN") (part "CONN-2-PIN")))
  )
  (nets
    (net (code "1") (name "+12V") (class "Default")
      (node (ref "C12") (pin "2") (pinfunction "2_2") (pintype "passive"))
      (node (ref "C14") (pin "1") (pinfunction "+_1") (pintype "passive"))
      (node (ref "C32") (pin "2") (pinfunction "2_2") (pintype "passive"))
      (node (ref "C33") (pin "1") (pinfunction "+_1") (pintype "passive"))
      (node (ref "D3") (pin "1") (pinfunction "C_1") (pintype "passive"))
      (node (ref "D7") (pin "1") (pinfunction "C_1") (pintype "passive"))
      (node (ref "L4") (pin "2") (pinfunction "2_2") (pintype "passive"))
      (node (ref "L7") (pin "2") (pinfunction "2_2") (pintype "passive"))
      (node (ref "Q1") (pin "3") (pinfunction "C_3") (pintype "passive"))
      (node (ref "Q3") (pin "3") (pinfunction "C_3") (pintype "passive"))
      (node (ref "Q7") (pin "3") (pinfunction "C_3") (pintype "passive"))
      (node (ref "Q9") (pin "3") (pinfunction "C_3") (pintype "passive"))
      (node (ref "R27") (pin "1") (pinfunction "1_1") (pintype "passive"))
      (node (ref "R28") (pin "2") (pinfunction "2_2") (pintype "passive"))
      (node (ref "R29") (pin "1") (pinfunction "1_1") (pintype "passive"))
      (node (ref "R31") (pin "2") (pinfunction "2_2") (pintype "passive"))
      (node (ref "R4") (pin "1") (pinfunction "1_1") (pintype "passive"))
      (node (ref "R5") (pin "1") (pinfunction "1_1") (pintype "passive"))
      (node (ref "R6") (pin "2") (pinfunction "2_2") (pintype "passive"))
      (node (ref "R8") (pin "2") (pinfunction "2_2") (pintype "passive"))
      (node (ref "T1") (pin "2") (pinfunction "2_2") (pintype "passive"))
      (node (ref "T1") (pin "3") (pinfunction "3_3") (pintype "passive"))
      (node (ref "T2") (pin "2") (pinfunction "2_2") (pintype "passive"))
      (node (ref "T2") (pin "3") (pinfunction "3_3") (pintype "passive"))
      (node (ref "TP1") (pin "1") (pinfunction "G9_1") (pintype "passive"))
      (node (ref "TP19") (pin "1") (pinfunction "G9_1") (pintype "passive"))
      (node (ref "VD2") (pin "2") (pinfunction "A_2") (pintype "passive"))
      (node (ref "VD5") (pin "2") (pinfunction "A_2") (pintype "passive"))
    )
    (net (code "2") (name "+15V") (class "Default")
      (node (ref "C5") (pin "1") (pinfunction "+_1") (pintype "passive"))
      (node (ref "C6") (pin "1") (pinfunction "+_1") (pintype "passive"))
      (node (ref "D5") (pin "1") (pinfunction "A_1") (pintype "passive"))
      (node (ref "L1") (pin "2") (pinfunction "2_2") (pintype "passive"))
      (node (ref "X3") (pin "1") (pinfunction "1_1") (pintype "passive"))
      (node (ref "X5") (pin "1") (pinfunction "1_1") (pintype "passive"))
    )
    (net (code "3") (name "+24V") (class "Default")
      (node (ref "C25") (pin "1") (pinfunction "+_1") (pintype "passive"))
      (node (ref "C26") (pin "1") (pinfunction "+_1") (pintype "passive"))
      (node (ref "D13") (pin "1") (pinfunction "A_1") (pintype "passive"))
      (node (ref "L5") (pin "2") (pinfunction "2_2") (pintype "passive"))
      (node (ref "X4") (pin "1") (pinfunction "1_1") (pintype "passive"))
      (node (ref "X6") (pin "1") (pinfunction "1_1") (pintype "passive"))
    )
    (net (code "4") (name "/B-1") (class "Default")
      (node (ref "C11") (pin "2") (pinfunction "2_2") (pintype "passive"))
      (node (ref "Q2") (pin "2") (pinfunction "D_2") (pintype "passive"))
      (node (ref "Q2") (pin "4") (pinfunction "D_4") (pintype "passive"))
      (node (ref "T1") (pin "1") (pinfunction "1_1") (pintype "passive"))
      (node (ref "TP5") (pin "1") (pinfunction "G9_1") (pintype "passive"))
      (node (ref "VD1") (pin "2") (pinfunction "A_2") (pintype "passive"))
    )
    (net (code "5") (name "/B-2") (class "Default")
      (node (ref "C15") (pin "1") (pinfunction "1_1") (pintype "passive"))
      (node (ref "Q4") (pin "2") (pinfunction "D_2") (pintype "passive"))
      (node (ref "Q4") (pin "4") (pinfunction "D_4") (pintype "passive"))
      (node (ref "T1") (pin "4") (pinfunction "4_4") (pintype "passive"))
      (node (ref "TP6") (pin "1") (pinfunction "G9_1") (pintype "passive"))
      (node (ref "VD3") (pin "1") (pinfunction "C_1") (pintype "passive"))
    )
    (net (code "6") (name "/B-3") (class "Default")
      (node (ref "C31") (pin "2") (pinfunction "2_2") (pintype "passive"))
      (node (ref "Q8") (pin "2") (pinfunction "D_2") (pintype "passive"))
      (node (ref "Q8") (pin "4") (pinfunction "D_4") (pintype "passive"))
      (node (ref "T2") (pin "1") (pinfunction "1_1") (pintype "passive"))
      (node (ref "TP22") (pin "1") (pinfunction "G9_1") (pintype "passive"))
      (node (ref "VD4") (pin "2") (pinfunction "A_2") (pintype "passive"))
    )
    (net (code "7") (name "/B-4") (class "Default")
      (node (ref "C35") (pin "1") (pinfunction "1_1") (pintype "passive"))
      (node (ref "Q10") (pin "2") (pinfunction "D_2") (pintype "passive"))
      (node (ref "Q10") (pin "4") (pinfunction "D_4") (pintype "passive"))
      (node (ref "T2") (pin "4") (pinfunction "4_4") (pintype "passive"))
      (node (ref "TP24") (pin "1") (pinfunction "G9_1") (pintype "passive"))
      (node (ref "VD6") (pin "1") (pinfunction "C_1") (pintype "passive"))
    )
    (net (code "8") (name "/G_1") (class "Default")
      (node (ref "R11") (pin "2") (pinfunction "2_2") (pintype "passive"))
      (node (ref "U1") (pin "9") (pinfunction "E1_9") (pintype "passive"))
    )
    (net (code "9") (name "/G_2") (class "Default")
      (node (ref "R20") (pin "2") (pinfunction "2_2") (pintype "passive"))
      (node (ref "U1") (pin "10") (pinfunction "E2_10") (pintype "passive"))
    )
    (net (code "10") (name "/G_3") (class "Default")
      (node (ref "R34") (pin "2") (pinfunction "2_2") (pintype "passive"))
      (node (ref "U3") (pin "9") (pinfunction "E1_9") (pintype "passive"))
    )
    (net (code "11") (name "/G_4") (class "Default")
      (node (ref "R36") (pin "2") (pinfunction "2_2") (pintype "passive"))
      (node (ref "U3") (pin "10") (pinfunction "E2_10") (pintype "passive"))
    )
    (net (code "12") (name "/I_FB") (class "Default")
      (node (ref "C24") (pin "2") (pinfunction "2_2") (pintype "passive"))
      (node (ref "R24") (pin "1") (pinfunction "1_1") (pintype "passive"))
      (node (ref "TP17") (pin "1") (pinfunction "G9_1") (pintype "passive"))
      (node (ref "U1") (pin "1") (pinfunction "1IN+_1") (pintype "input"))
    )
    (net (code "13") (name "/I_FB_1") (class "Default")
      (node (ref "C44") (pin "2") (pinfunction "2_2") (pintype "passive"))
      (node (ref "R47") (pin "1") (pinfunction "1_1") (pintype "passive"))
      (node (ref "TP35") (pin "1") (pinfunction "G9_1") (pintype "passive"))
      (node (ref "U3") (pin "1") (pinfunction "1IN+_1") (pintype "input"))
    )
    (net (code "14") (name "/T1-1") (class "Default")
      (node (ref "D1") (pin "1") (pinfunction "C_1") (pintype "passive"))
      (node (ref "D2") (pin "2") (pinfunction "A_2") (pintype "passive"))
      (node (ref "T1") (pin "5") (pinfunction "5_5") (pintype "passive"))
    )
    (net (code "15") (name "/T1-2") (class "Default")
      (node (ref "D4") (pin "2") (pinfunction "A_2") (pintype "passive"))
      (node (ref "D8") (pin "1") (pinfunction "C_1") (pintype "passive"))
      (node (ref "T1") (pin "8") (pinfunction "8_8") (pintype "passive"))
    )
    (net (code "16") (name "/T2-1") (class "Default")
      (node (ref "D10") (pin "1") (pinfunction "C_1") (pintype "passive"))
      (node (ref "D11") (pin "2") (pinfunction "A_2") (pintype "passive"))
      (node (ref "T2") (pin "5") (pinfunction "5_5") (pintype "passive"))
    )
    (net (code "17") (name "/T2-2") (class "Default")
      (node (ref "D12") (pin "2") (pinfunction "A_2") (pintype "passive"))
      (node (ref "D14") (pin "1") (pinfunction "C_1") (pintype "passive"))
      (node (ref "T2") (pin "8") (pinfunction "8_8") (pintype "passive"))
    )
    (net (code "18") (name "/VCC_IC") (class "Default")
      (node (ref "C17") (pin "1") (pinfunction "+_1") (pintype "passive"))
      (node (ref "C22") (pin "2") (pinfunction "2_2") (pintype "passive"))
      (node (ref "L4") (pin "1") (pinfunction "1_1") (pintype "passive"))
      (node (ref "TP11") (pin "1") (pinfunction "G9_1") (pintype "passive"))
      (node (ref "U1") (pin "12") (pinfunction "VCC_12") (pintype "power_in"))
    )
    (net (code "19") (name "/VCC_IC_1") (class "Default")
      (node (ref "C37") (pin "1") (pinfunction "+_1") (pintype "passive"))
      (node (ref "C42") (pin "2") (pinfunction "2_2") (pintype "passive"))
      (node (ref "L7") (pin "1") (pinfunction "1_1") (pintype "passive"))
      (node (ref "TP31") (pin "1") (pinfunction "G9_1") (pintype "passive"))
      (node (ref "U3") (pin "12") (pinfunction "VCC_12") (pintype "power_in"))
    )
    (net (code "20") (name "BAT") (class "Default")
      (node (ref "C1") (pin "1") (pinfunction "+_1") (pintype "passive"))
      (node (ref "C2") (pin "1") (pinfunction "+_1") (pintype "passive"))
      (node (ref "DD1") (pin "1") (pinfunction "VIN_1") (pintype "passive"))
      (node (ref "X2") (pin "1") (pinfunction "1_1") (pintype "passive"))
    )
    (net (code "21") (name "BAT_GND") (class "Default")
      (node (ref "C1") (pin "2") (pinfunction "-_2") (pintype "passive"))
      (node (ref "C10") (pin "2") (pinfunction "-_2") (pintype "passive"))
      (node (ref "C12") (pin "1") (pinfunction "1_1") (pintype "passive"))
      (node (ref "C14") (pin "2") (pinfunction "-_2") (pintype "passive"))
      (node (ref "C17") (pin "2") (pinfunction "-_2") (pintype "passive"))
      (node (ref "C18") (pin "2") (pinfunction "2_2") (pintype "passive"))
      (node (ref "C19") (pin "2") (pinfunction "2_2") (pintype "passive"))
      (node (ref "C2") (pin "2") (pinfunction "-_2") (pintype "passive"))
      (node (ref "C20") (pin "2") (pinfunction "-_2") (pintype "passive"))
      (node (ref "C21") (pin "1") (pinfunction "1_1") (pintype "passive"))
      (node (ref "C22") (pin "1") (pinfunction "1_1") (pintype "passive"))
      (node (ref "C23") (pin "1") (pinfunction "1_1") (pintype "passive"))
      (node (ref "C24") (pin "1") (pinfunction "1_1") (pintype "passive"))
      (node (ref "C3") (pin "2") (pinfunction "-_2") (pintype "passive"))
      (node (ref "C32") (pin "1") (pinfunction "1_1") (pintype "passive"))
      (node (ref "C33") (pin "2") (pinfunction "-_2") (pintype "passive"))
      (node (ref "C37") (pin "2") (pinfunction "-_2") (pintype "passive"))
      (node (ref "C38") (pin "2") (pinfunction "2_2") (pintype "passive"))
      (node (ref "C39") (pin "2") (pinfunction "2_2") (pintype "passive"))
      (node (ref "C4") (pin "2") (pinfunction "2_2") (pintype "passive"))
      (node (ref "C40") (pin "2") (pinfunction "-_2") (pintype "passive"))
      (node (ref "C41") (pin "1") (pinfunction "1_1") (pintype "passive"))
      (node (ref "C42") (pin "1") (pinfunction "1_1") (pintype "passive"))
      (node (ref "C43") (pin "1") (pinfunction "1_1") (pintype "passive"))
      (node (ref "C44") (pin "1") (pinfunction "1_1") (pintype "passive"))
      (node (ref "C5") (pin "2") (pinfunction "-_2") (pintype "passive"))
      (node (ref "C6") (pin "2") (pinfunction "-_2") (pintype "passive"))
      (node (ref "C8") (pin "2") (pinfunction "-_2") (pintype "passive"))
      (node (ref "C9") (pin "2") (pinfunction "-_2") (pintype "passive"))
      (node (ref "D6") (pin "2") (pinfunction "A_2") (pintype "passive"))
      (node (ref "DD1") (pin "3") (pinfunction "GND_3") (pintype "passive"))
      (node (ref "DD1") (pin "5") (pinfunction "ON/OFF_5") (pintype "passive"))
      (node (ref "L3") (pin "2") (pinfunction "2_2") (pintype "passive"))
      (node (ref "Q11") (pin "3") (pinfunction "C_3") (pintype "passive"))
      (node (ref "Q12") (pin "3") (pinfunction "C_3") (pintype "passive"))
      (node (ref "Q5") (pin "3") (pinfunction "C_3") (pintype "passive"))
      (node (ref "Q6") (pin "3") (pinfunction "C_3") (pintype "passive"))
      (node (ref "R1") (pin "1") (pinfunction "1_1") (pintype "passive"))
      (node (ref "R10") (pin "1") (pinfunction "1_1") (pintype "passive"))
      (node (ref "R13") (pin "2") (pinfunction "2_2") (pintype "passive"))
      (node (ref "R14") (pin "2") (pinfunction "2_2") (pintype "passive"))
      (node (ref "R16") (pin "2") (pinfunction "2_2") (pintype "passive"))
      (node (ref "R17") (pin "2") (pinfunction "2_2") (pintype "passive"))
      (node (ref "R19") (pin "1") (pinfunction "1_1") (pintype "passive"))
      (node (ref "R22") (pin "1") (pinfunction "1_1") (pintype "passive"))
      (node (ref "R23") (pin "1") (pinfunction "1_1") (pintype "passive"))
      (node (ref "R25") (pin "1") (pinfunction "1_1") (pintype "passive"))
      (node (ref "R3") (pin "1") (pinfunction "1_1") (pintype "passive"))
      (node (ref "R33") (pin "1") (pinfunction "1_1") (pintype "passive"))
      (node (ref "R38") (pin "2") (pinfunction "2_2") (pintype "passive"))
      (node (ref "R39") (pin "2") (pinfunction "2_2") (pintype "passive"))
      (node (ref "R40") (pin "1") (pinfunction "1_1") (pintype "passive"))
      (node (ref "R42") (pin "2") (pinfunction "2_2") (pintype "passive"))
      (node (ref "R43") (pin "2") (pinfunction "2_2") (pintype "passive"))
      (node (ref "R45") (pin "1") (pinfunction "1_1") (pintype "passive"))
      (node (ref "R46") (pin "1") (pinfunction "1_1") (pintype "passive"))
      (node (ref "R48") (pin "1") (pinfunction "1_1") (pintype "passive"))
      (node (ref "U1") (pin "7") (pinfunction "GND_7") (pintype "power_in"))
      (node (ref "U2") (pin "3") (pinfunction "A_3") (pintype "passive"))
      (node (ref "U3") (pin "7") (pinfunction "GND_7") (pintype "power_in"))
      (node (ref "U4") (pin "3") (pinfunction "A_3") (pintype "passive"))
      (node (ref "VD1") (pin "1") (pinfunction "C_1") (pintype "passive"))
      (node (ref "VD2") (pin "1") (pinfunction "C_1") (pintype "passive"))
      (node (ref "VD3") (pin "2") (pinfunction "A_2") (pintype "passive"))
      (node (ref "VD4") (pin "1") (pinfunction "C_1") (pintype "passive"))
      (node (ref "VD5") (pin "1") (pinfunction "C_1") (pintype "passive"))
      (node (ref "VD6") (pin "2") (pinfunction "A_2") (pintype "passive"))
      (node (ref "X1") (pin "2") (pinfunction "2_2") (pintype "passive"))
      (node (ref "X2") (pin "2") (pinfunction "2_2") (pintype "passive"))
      (node (ref "X3") (pin "2") (pinfunction "2_2") (pintype "passive"))
      (node (ref "X5") (pin "2") (pinfunction "2_2") (pintype "passive"))
    )
    (net (code "22") (name "GND_1") (class "Default")
      (node (ref "C25") (pin "2") (pinfunction "-_2") (pintype "passive"))
      (node (ref "C26") (pin "2") (pinfunction "-_2") (pintype "passive"))
      (node (ref "L6") (pin "2") (pinfunction "2_2") (pintype "passive"))
      (node (ref "R26") (pin "1") (pinfunction "1_1") (pintype "passive"))
      (node (ref "X4") (pin "2") (pinfunction "2_2") (pintype "passive"))
      (node (ref "X6") (pin "2") (pinfunction "2_2") (pintype "passive"))
    )
    (net (code "23") (name "Net-(C7-+)") (class "Default")
      (node (ref "C7") (pin "1") (pinfunction "+_1") (pintype "passive"))
      (node (ref "D2") (pin "1") (pinfunction "C_1") (pintype "passive"))
      (node (ref "D4") (pin "1") (pinfunction "C_1") (pintype "passive"))
      (node (ref "L1") (pin "1") (pinfunction "1_1") (pintype "passive"))
    )
    (net (code "24") (name "Net-(C7--)") (class "Default")
      (node (ref "C7") (pin "2") (pinfunction "-_2") (pintype "passive"))
      (node (ref "D1") (pin "2") (pinfunction "A_2") (pintype "passive"))
      (node (ref "D8") (pin "2") (pinfunction "A_2") (pintype "passive"))
      (node (ref "L3") (pin "1") (pinfunction "1_1") (pintype "passive"))
    )
    (net (code "25") (name "Net-(C10-+)") (class "Default")
      (node (ref "C10") (pin "1") (pinfunction "+_1") (pintype "passive"))
      (node (ref "C3") (pin "1") (pinfunction "+_1") (pintype "passive"))
      (node (ref "C4") (pin "1") (pinfunction "1_1") (pintype "passive"))
      (node (ref "C8") (pin "1") (pinfunction "+_1") (pintype "passive"))
      (node (ref "C9") (pin "1") (pinfunction "+_1") (pintype "passive"))
      (node (ref "D3") (pin "2") (pinfunction "A_2") (pintype "passive"))
      (node (ref "L2") (pin "2") (pinfunction "2_2") (pintype "passive"))
      (node (ref "R2") (pin "2") (pinfunction "2_2") (pintype "passive"))
    )
    (net (code "26") (name "Net-(C11-Pad1)") (class "Default")
      (node (ref "C11") (pin "1") (pinfunction "1_1") (pintype "passive"))
      (node (ref "R4") (pin "2") (pinfunction "2_2") (pintype "passive"))
    )
    (net (code "27") (name "Net-(C15-Pad2)") (class "Default")
      (node (ref "C15") (pin "2") (pinfunction "2_2") (pintype "passive"))
      (node (ref "R6") (pin "1") (pinfunction "1_1") (pintype "passive"))
    )
    (net (code "28") (name "Net-(C20-+)") (class "Default")
      (node (ref "C20") (pin "1") (pinfunction "+_1") (pintype "passive"))
      (node (ref "C21") (pin "2") (pinfunction "2_2") (pintype "passive"))
      (node (ref "R15") (pin "2") (pinfunction "2_2") (pintype "passive"))
      (node (ref "R18") (pin "2") (pinfunction "2_2") (pintype "passive"))
      (node (ref "TP15") (pin "1") (pinfunction "G9_1") (pintype "passive"))
      (node (ref "U1") (pin "13") (pinfunction "OUTPUT_CTRL_13") (pintype "input"))
      (node (ref "U1") (pin "14") (pinfunction "REF_14") (pintype "output"))
    )
    (net (code "29") (name "Net-(C27-+)") (class "Default")
      (node (ref "C27") (pin "1") (pinfunction "+_1") (pintype "passive"))
      (node (ref "D11") (pin "1") (pinfunction "C_1") (pintype "passive"))
      (node (ref "D12") (pin "1") (pinfunction "C_1") (pintype "passive"))
      (node (ref "L5") (pin "1") (pinfunction "1_1") (pintype "passive"))
    )
    (net (code "30") (name "Net-(C27--)") (class "Default")
      (node (ref "C27") (pin "2") (pinfunction "-_2") (pintype "passive"))
      (node (ref "D10") (pin "2") (pinfunction "A_2") (pintype "passive"))
      (node (ref "D14") (pin "2") (pinfunction "A_2") (pintype "passive"))
      (node (ref "L6") (pin "1") (pinfunction "1_1") (pintype "passive"))
    )
    (net (code "31") (name "Net-(C31-Pad1)") (class "Default")
      (node (ref "C31") (pin "1") (pinfunction "1_1") (pintype "passive"))
      (node (ref "R27") (pin "2") (pinfunction "2_2") (pintype "passive"))
    )
    (net (code "32") (name "Net-(C35-Pad2)") (class "Default")
      (node (ref "C35") (pin "2") (pinfunction "2_2") (pintype "passive"))
      (node (ref "R28") (pin "1") (pinfunction "1_1") (pintype "passive"))
    )
    (net (code "33") (name "Net-(C40-+)") (class "Default")
      (node (ref "C40") (pin "1") (pinfunction "+_1") (pintype "passive"))
      (node (ref "C41") (pin "2") (pinfunction "2_2") (pintype "passive"))
      (node (ref "R41") (pin "2") (pinfunction "2_2") (pintype "passive"))
      (node (ref "R44") (pin "2") (pinfunction "2_2") (pintype "passive"))
      (node (ref "TP33") (pin "1") (pinfunction "G9_1") (pintype "passive"))
      (node (ref "U3") (pin "13") (pinfunction "OUTPUT_CTRL_13") (pintype "input"))
      (node (ref "U3") (pin "14") (pinfunction "REF_14") (pintype "output"))
    )
    (net (code "34") (name "Net-(D5-K)") (class "Default")
      (node (ref "D5") (pin "2") (pinfunction "K_2") (pintype "passive"))
      (node (ref "R3") (pin "2") (pinfunction "2_2") (pintype "passive"))
    )
    (net (code "35") (name "Net-(D6-C)") (class "Default")
      (node (ref "D6") (pin "1") (pinfunction "C_1") (pintype "passive"))
      (node (ref "DD1") (pin "2") (pinfunction "OUT_2") (pintype "passive"))
      (node (ref "L2") (pin "1") (pinfunction "1_1") (pintype "passive"))
    )
    (net (code "36") (name "Net-(D7-A)") (class "Default")
      (node (ref "D7") (pin "2") (pinfunction "A_2") (pintype "passive"))
      (node (ref "X1") (pin "1") (pinfunction "1_1") (pintype "passive"))
    )
    (net (code "37") (name "Net-(D9-A)") (class "Default")
      (node (ref "C13") (pin "2") (pinfunction "2_2") (pintype "passive"))
      (node (ref "C16") (pin "1") (pinfunction "1_1") (pintype "passive"))
      (node (ref "D9") (pin "1") (pinfunction "A_1") (pintype "passive"))
      (node (ref "R7") (pin "2") (pinfunction "2_2") (pintype "passive"))
      (node (ref "R9") (pin "1") (pinfunction "1_1") (pintype "passive"))
      (node (ref "TP4") (pin "1") (pinfunction "G9_1") (pintype "passive"))
      (node (ref "U1") (pin "3") (pinfunction "FEEDBACK_3") (pintype "input"))
    )
    (net (code "38") (name "Net-(D9-K)") (class "Default")
      (node (ref "D9") (pin "2") (pinfunction "K_2") (pintype "passive"))
      (node (ref "R10") (pin "2") (pinfunction "2_2") (pintype "passive"))
    )
    (net (code "39") (name "Net-(D13-K)") (class "Default")
      (node (ref "D13") (pin "2") (pinfunction "K_2") (pintype "passive"))
      (node (ref "R26") (pin "2") (pinfunction "2_2") (pintype "passive"))
    )
    (net (code "40") (name "Net-(D15-A)") (class "Default")
      (node (ref "C34") (pin "2") (pinfunction "2_2") (pintype "passive"))
      (node (ref "C36") (pin "1") (pinfunction "1_1") (pintype "passive"))
      (node (ref "D15") (pin "1") (pinfunction "A_1") (pintype "passive"))
      (node (ref "R30") (pin "2") (pinfunction "2_2") (pintype "passive"))
      (node (ref "R32") (pin "1") (pinfunction "1_1") (pintype "passive"))
      (node (ref "TP23") (pin "1") (pinfunction "G9_1") (pintype "passive"))
      (node (ref "U3") (pin "3") (pinfunction "FEEDBACK_3") (pintype "input"))
    )
    (net (code "41") (name "Net-(D15-K)") (class "Default")
      (node (ref "D15") (pin "2") (pinfunction "K_2") (pintype "passive"))
      (node (ref "R33") (pin "2") (pinfunction "2_2") (pintype "passive"))
    )
    (net (code "42") (name "Net-(DD1-FEEDBACK)") (class "Default")
      (node (ref "DD1") (pin "4") (pinfunction "FEEDBACK_4") (pintype "passive"))
      (node (ref "R1") (pin "2") (pinfunction "2_2") (pintype "passive"))
      (node (ref "R2") (pin "1") (pinfunction "1_1") (pintype "passive"))
    )
    (net (code "43") (name "Net-(Q1-B)") (class "Default")
      (node (ref "Q1") (pin "1") (pinfunction "B_1") (pintype "passive"))
      (node (ref "Q5") (pin "1") (pinfunction "B_1") (pintype "passive"))
      (node (ref "R11") (pin "1") (pinfunction "1_1") (pintype "passive"))
      (node (ref "R22") (pin "2") (pinfunction "2_2") (pintype "passive"))
      (node (ref "TP9") (pin "1") (pinfunction "G9_1") (pintype "passive"))
    )
    (net (code "44") (name "Net-(Q1-E)") (class "Default")
      (node (ref "Q1") (pin "2") (pinfunction "E_2") (pintype "passive"))
      (node (ref "Q5") (pin "2") (pinfunction "E_2") (pintype "passive"))
      (node (ref "R12") (pin "1") (pinfunction "1_1") (pintype "passive"))
    )
    (net (code "45") (name "Net-(Q2-G)") (class "Default")
      (node (ref "Q2") (pin "1") (pinfunction "G_1") (pintype "passive"))
      (node (ref "R12") (pin "2") (pinfunction "2_2") (pintype "passive"))
      (node (ref "TP10") (pin "1") (pinfunction "G9_1") (pintype "passive"))
    )
    (net (code "46") (name "Net-(Q2-S)") (class "Default")
      (node (ref "C23") (pin "2") (pinfunction "2_2") (pintype "passive"))
      (node (ref "Q2") (pin "3") (pinfunction "S_3") (pintype "passive"))
      (node (ref "Q4") (pin "3") (pinfunction "S_3") (pintype "passive"))
      (node (ref "R24") (pin "2") (pinfunction "2_2") (pintype "passive"))
      (node (ref "R25") (pin "2") (pinfunction "2_2") (pintype "passive"))
      (node (ref "TP18") (pin "1") (pinfunction "G9_1") (pintype "passive"))
    )
    (net (code "47") (name "Net-(Q3-B)") (class "Default")
      (node (ref "Q3") (pin "1") (pinfunction "B_1") (pintype "passive"))
      (node (ref "Q6") (pin "1") (pinfunction "B_1") (pintype "passive"))
      (node (ref "R20") (pin "1") (pinfunction "1_1") (pintype "passive"))
      (node (ref "R23") (pin "2") (pinfunction "2_2") (pintype "passive"))
      (node (ref "TP14") (pin "1") (pinfunction "G9_1") (pintype "passive"))
    )
    (net (code "48") (name "Net-(Q3-E)") (class "Default")
      (node (ref "Q3") (pin "2") (pinfunction "E_2") (pintype "passive"))
      (node (ref "Q6") (pin "2") (pinfunction "E_2") (pintype "passive"))
      (node (ref "R21") (pin "1") (pinfunction "1_1") (pintype "passive"))
    )
    (net (code "49") (name "Net-(Q4-G)") (class "Default")
      (node (ref "Q4") (pin "1") (pinfunction "G_1") (pintype "passive"))
      (node (ref "R21") (pin "2") (pinfunction "2_2") (pintype "passive"))
      (node (ref "TP13") (pin "1") (pinfunction "G9_1") (pintype "passive"))
    )
    (net (code "50") (name "Net-(Q8-G)") (class "Default")
      (node (ref "Q8") (pin "1") (pinfunction "G_1") (pintype "passive"))
      (node (ref "R35") (pin "2") (pinfunction "2_2") (pintype "passive"))
      (node (ref "TP27") (pin "1") (pinfunction "G9_1") (pintype "passive"))
    )
    (net (code "51") (name "Net-(Q10-G)") (class "Default")
      (node (ref "Q10") (pin "1") (pinfunction "G_1") (pintype "passive"))
      (node (ref "R37") (pin "2") (pinfunction "2_2") (pintype "passive"))
      (node (ref "TP29") (pin "1") (pinfunction "G9_1") (pintype "passive"))
    )
    (net (code "52") (name "Net-(Q10-S)") (class "Default")
      (node (ref "C43") (pin "2") (pinfunction "2_2") (pintype "passive"))
      (node (ref "Q10") (pin "3") (pinfunction "S_3") (pintype "passive"))
      (node (ref "Q8") (pin "3") (pinfunction "S_3") (pintype "passive"))
      (node (ref "R47") (pin "2") (pinfunction "2_2") (pintype "passive"))
      (node (ref "R48") (pin "2") (pinfunction "2_2") (pintype "passive"))
      (node (ref "TP36") (pin "1") (pinfunction "G9_1") (pintype "passive"))
    )
    (net (code "53") (name "Net-(Q11-B)") (class "Default")
      (node (ref "Q11") (pin "1") (pinfunction "B_1") (pintype "passive"))
      (node (ref "Q7") (pin "1") (pinfunction "B_1") (pintype "passive"))
      (node (ref "R34") (pin "1") (pinfunction "1_1") (pintype "passive"))
      (node (ref "R40") (pin "2") (pinfunction "2_2") (pintype "passive"))
      (node (ref "TP25") (pin "1") (pinfunction "G9_1") (pintype "passive"))
    )
    (net (code "54") (name "Net-(Q11-E)") (class "Default")
      (node (ref "Q11") (pin "2") (pinfunction "E_2") (pintype "passive"))
      (node (ref "Q7") (pin "2") (pinfunction "E_2") (pintype "passive"))
      (node (ref "R35") (pin "1") (pinfunction "1_1") (pintype "passive"))
    )
    (net (code "55") (name "Net-(Q12-B)") (class "Default")
      (node (ref "Q12") (pin "1") (pinfunction "B_1") (pintype "passive"))
      (node (ref "Q9") (pin "1") (pinfunction "B_1") (pintype "passive"))
      (node (ref "R36") (pin "1") (pinfunction "1_1") (pintype "passive"))
      (node (ref "R46") (pin "2") (pinfunction "2_2") (pintype "passive"))
      (node (ref "TP30") (pin "1") (pinfunction "G9_1") (pintype "passive"))
    )
    (net (code "56") (name "Net-(Q12-E)") (class "Default")
      (node (ref "Q12") (pin "2") (pinfunction "E_2") (pintype "passive"))
      (node (ref "Q9") (pin "2") (pinfunction "E_2") (pintype "passive"))
      (node (ref "R37") (pin "1") (pinfunction "1_1") (pintype "passive"))
    )
    (net (code "57") (name "Net-(T1-Pad6)") (class "Default")
      (node (ref "T1") (pin "6") (pinfunction "6_6") (pintype "passive"))
      (node (ref "T1") (pin "7") (pinfunction "7_7") (pintype "passive"))
    )
    (net (code "58") (name "Net-(T2-Pad6)") (class "Default")
      (node (ref "T2") (pin "6") (pinfunction "6_6") (pintype "passive"))
      (node (ref "T2") (pin "7") (pinfunction "7_7") (pintype "passive"))
    )
    (net (code "59") (name "Net-(TP2-G9)") (class "Default")
      (node (ref "C13") (pin "1") (pinfunction "1_1") (pintype "passive"))
      (node (ref "R15") (pin "1") (pinfunction "1_1") (pintype "passive"))
      (node (ref "R16") (pin "1") (pinfunction "1_1") (pintype "passive"))
      (node (ref "R7") (pin "1") (pinfunction "1_1") (pintype "passive"))
      (node (ref "TP2") (pin "1") (pinfunction "G9_1") (pintype "passive"))
      (node (ref "U1") (pin "2") (pinfunction "1IN-_2") (pintype "input"))
    )
    (net (code "60") (name "Net-(TP3-G9)") (class "Default")
      (node (ref "C19") (pin "1") (pinfunction "1_1") (pintype "passive"))
      (node (ref "R14") (pin "1") (pinfunction "1_1") (pintype "passive"))
      (node (ref "R5") (pin "2") (pinfunction "2_2") (pintype "passive"))
      (node (ref "TP3") (pin "1") (pinfunction "G9_1") (pintype "passive"))
      (node (ref "U1") (pin "16") (pinfunction "2IN+_16") (pintype "input"))
    )
    (net (code "61") (name "Net-(TP7-G9)") (class "Default")
      (node (ref "C16") (pin "2") (pinfunction "2_2") (pintype "passive"))
      (node (ref "R17") (pin "1") (pinfunction "1_1") (pintype "passive"))
      (node (ref "R18") (pin "1") (pinfunction "1_1") (pintype "passive"))
      (node (ref "R9") (pin "2") (pinfunction "2_2") (pintype "passive"))
      (node (ref "TP7") (pin "1") (pinfunction "G9_1") (pintype "passive"))
      (node (ref "U1") (pin "15") (pinfunction "2IN-_15") (pintype "input"))
      (node (ref "U2") (pin "1") (pinfunction "C_1") (pintype "passive"))
      (node (ref "U2") (pin "2") (pinfunction "REF_2") (pintype "passive"))
    )
    (net (code "62") (name "Net-(TP8-G9)") (class "Default")
      (node (ref "R13") (pin "1") (pinfunction "1_1") (pintype "passive"))
      (node (ref "TP8") (pin "1") (pinfunction "G9_1") (pintype "passive"))
      (node (ref "U1") (pin "6") (pinfunction "RT_6") (pintype "passive"))
    )
    (net (code "63") (name "Net-(TP12-G9)") (class "Default")
      (node (ref "C18") (pin "1") (pinfunction "1_1") (pintype "passive"))
      (node (ref "TP12") (pin "1") (pinfunction "G9_1") (pintype "passive"))
      (node (ref "U1") (pin "5") (pinfunction "CT_5") (pintype "passive"))
    )
    (net (code "64") (name "Net-(TP20-G9)") (class "Default")
      (node (ref "C34") (pin "1") (pinfunction "1_1") (pintype "passive"))
      (node (ref "R30") (pin "1") (pinfunction "1_1") (pintype "passive"))
      (node (ref "R41") (pin "1") (pinfunction "1_1") (pintype "passive"))
      (node (ref "R42") (pin "1") (pinfunction "1_1") (pintype "passive"))
      (node (ref "TP20") (pin "1") (pinfunction "G9_1") (pintype "passive"))
      (node (ref "U3") (pin "2") (pinfunction "1IN-_2") (pintype "input"))
    )
    (net (code "65") (name "Net-(TP21-G9)") (class "Default")
      (node (ref "C39") (pin "1") (pinfunction "1_1") (pintype "passive"))
      (node (ref "R29") (pin "2") (pinfunction "2_2") (pintype "passive"))
      (node (ref "R39") (pin "1") (pinfunction "1_1") (pintype "passive"))
      (node (ref "TP21") (pin "1") (pinfunction "G9_1") (pintype "passive"))
      (node (ref "U3") (pin "16") (pinfunction "2IN+_16") (pintype "input"))
    )
    (net (code "66") (name "Net-(TP26-G9)") (class "Default")
      (node (ref "C36") (pin "2") (pinfunction "2_2") (pintype "passive"))
      (node (ref "R32") (pin "2") (pinfunction "2_2") (pintype "passive"))
      (node (ref "R43") (pin "1") (pinfunction "1_1") (pintype "passive"))
      (node (ref "R44") (pin "1") (pinfunction "1_1") (pintype "passive"))
      (node (ref "TP26") (pin "1") (pinfunction "G9_1") (pintype "passive"))
      (node (ref "U3") (pin "15") (pinfunction "2IN-_15") (pintype "input"))
      (node (ref "U4") (pin "1") (pinfunction "C_1") (pintype "passive"))
      (node (ref "U4") (pin "2") (pinfunction "REF_2") (pintype "passive"))
    )
    (net (code "67") (name "Net-(TP28-G9)") (class "Default")
      (node (ref "R38") (pin "1") (pinfunction "1_1") (pintype "passive"))
      (node (ref "TP28") (pin "1") (pinfunction "G9_1") (pintype "passive"))
      (node (ref "U3") (pin "6") (pinfunction "RT_6") (pintype "passive"))
    )
    (net (code "68") (name "Net-(TP32-G9)") (class "Default")
      (node (ref "C38") (pin "1") (pinfunction "1_1") (pintype "passive"))
      (node (ref "TP32") (pin "1") (pinfunction "G9_1") (pintype "passive"))
      (node (ref "U3") (pin "5") (pinfunction "CT_5") (pintype "passive"))
    )
    (net (code "69") (name "Net-(U1-C1)") (class "Default")
      (node (ref "R8") (pin "1") (pinfunction "1_1") (pintype "passive"))
      (node (ref "U1") (pin "11") (pinfunction "C2_11") (pintype "passive"))
      (node (ref "U1") (pin "8") (pinfunction "C1_8") (pintype "passive"))
    )
    (net (code "70") (name "Net-(U1-DTC)") (class "Default")
      (node (ref "R19") (pin "2") (pinfunction "2_2") (pintype "passive"))
      (node (ref "U1") (pin "4") (pinfunction "DTC_4") (pintype "input"))
    )
    (net (code "71") (name "Net-(U3-C1)") (class "Default")
      (node (ref "R31") (pin "1") (pinfunction "1_1") (pintype "passive"))
      (node (ref "U3") (pin "11") (pinfunction "C2_11") (pintype "passive"))
      (node (ref "U3") (pin "8") (pinfunction "C1_8") (pintype "passive"))
    )
    (net (code "72") (name "Net-(U3-DTC)") (class "Default")
      (node (ref "R45") (pin "2") (pinfunction "2_2") (pintype "passive"))
      (node (ref "U3") (pin "4") (pinfunction "DTC_4") (pintype "input"))
    )
  )
)
